# LoRa.net
KiCad netlist of a schematic drawn in Altium Designer
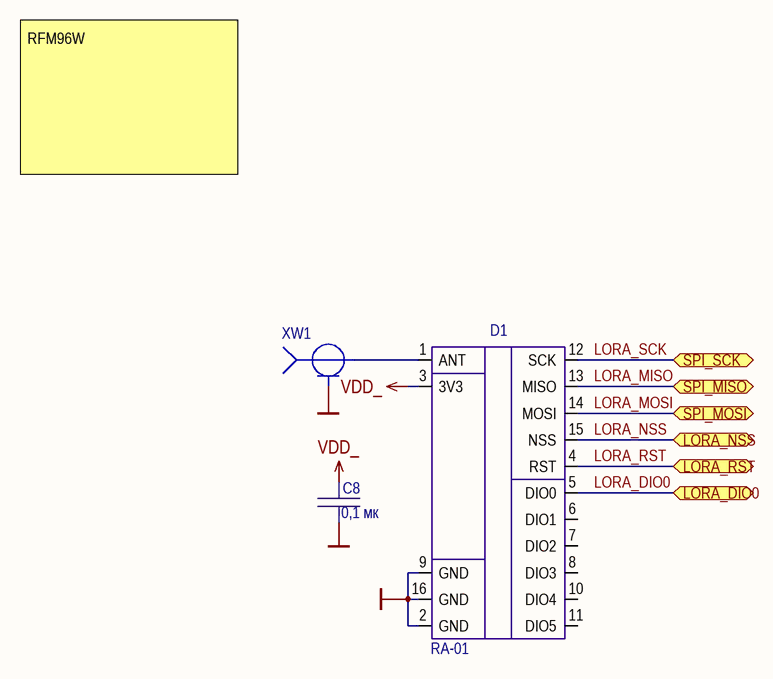
[diagram p0: LoRa.SchDoc]

(export (version "E")
  (design (tool "Eeschema 10.0.6"))
  (components
    (comp (ref "C8")
      (value "0,1 мк")
      (footprint "C_0603")
      (description "CAP CER 0.1UF 100V X7R 0603")
      (fields
        (field (name "PART NUMBER") "GRM188R72A104MA35D")
        (field (name "MANUFACTURER") "Murata Electronics")
      )
      (libsource (lib "Database_Lib") (part "Capasitor"))
    )
    (comp (ref "D1")
      (value "RA-01")
      (footprint "RA-02")
      (description "LoRa modem")
      (libsource (lib "8. Other") (part "RA-01"))
    )
    (comp (ref "XW1")
      (value "HYR-1139-RP")
      (footprint "SMA (HYR1139)")
      (libsource (lib "7. Connectors") (part "HYR-1139-RP"))
    )
  )
  (nets
    (net (code "1") (name "/LORA_DIO0") (class "Default")
      (node (ref "D1") (pin "5") (pinfunction "DIO0_5") (pintype "passive"))
    )
    (net (code "2") (name "/LORA_MISO") (class "Default")
      (node (ref "D1") (pin "13") (pinfunction "MISO_13") (pintype "passive"))
    )
    (net (code "3") (name "/LORA_MOSI") (class "Default")
      (node (ref "D1") (pin "14") (pinfunction "MOSI_14") (pintype "passive"))
    )
    (net (code "4") (name "/LORA_NSS") (class "Default")
      (node (ref "D1") (pin "15") (pinfunction "NSS_15") (pintype "passive"))
    )
    (net (code "5") (name "/LORA_RST") (class "Default")
      (node (ref "D1") (pin "4") (pinfunction "RST_4") (pintype "passive"))
    )
    (net (code "6") (name "/LORA_SCK") (class "Default")
      (node (ref "D1") (pin "12") (pinfunction "SCK_12") (pintype "passive"))
    )
    (net (code "7") (name "GND") (class "Default")
      (node (ref "D1") (pin "16") (pinfunction "GND_16") (pintype "passive"))
      (node (ref "D1") (pin "2") (pinfunction "GND_2") (pintype "passive"))
      (node (ref "D1") (pin "9") (pinfunction "GND_9") (pintype "passive"))
      (node (ref "XW1") (pin "1") (pinfunction "1_1") (pintype "passive"))
    )
    (net (code "8") (name "Net-(D1-ANT)") (class "Default")
      (node (ref "D1") (pin "1") (pinfunction "ANT_1") (pintype "passive"))
      (node (ref "XW1") (pin "2") (pinfunction "2_2") (pintype "passive"))
    )
    (net (code "9") (name "VDD_") (class "Default")
      (node (ref "C8") (pin "2") (pinfunction "2_2") (pintype "passive"))
      (node (ref "D1") (pin "3") (pinfunction "3V3_3") (pintype "passive"))
    )
    (net (code "10") (name "unconnected-(C8-Pad1)") (class "Default")
      (node (ref "C8") (pin "1") (pinfunction "1_1") (pintype "passive"))
    )
    (net (code "11") (name "unconnected-(D1-DIO1-Pad6)") (class "Default")
      (node (ref "D1") (pin "6") (pinfunction "DIO1_6") (pintype "passive"))
    )
    (net (code "12") (name "unconnected-(D1-DIO2-Pad7)") (class "Default")
      (node (ref "D1") (pin "7") (pinfunction "DIO2_7") (pintype "passive"))
    )
    (net (code "13") (name "unconnected-(D1-DIO3-Pad8)") (class "Default")
      (node (ref "D1") (pin "8") (pinfunction "DIO3_8") (pintype "passive"))
    )
    (net (code "14") (name "unconnected-(D1-DIO4-Pad10)") (class "Default")
      (node (ref "D1") (pin "10") (pinfunction "DIO4_10") (pintype "passive"))
    )
    (net (code "15") (name "unconnected-(D1-DIO5-Pad11)") (class "Default")
      (node (ref "D1") (pin "11") (pinfunction "DIO5_11") (pintype "passive"))
    )
  )
)
